# PDM-S05-V00-TempSensor.net
KiCad netlist of a schematic drawn in Altium Designer
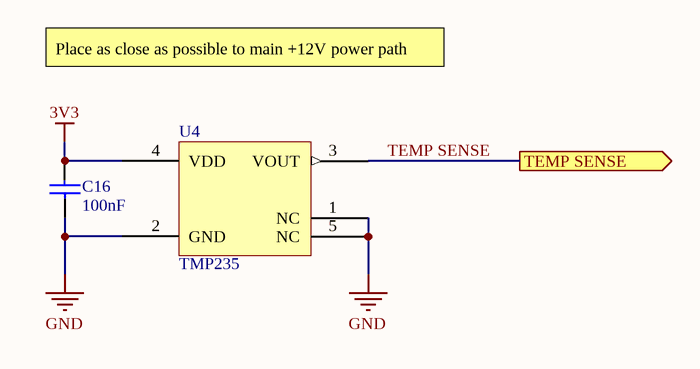
[diagram p0: PDM-S05-V00-TempSensor.SchDoc]

(export (version "E")
  (design (tool "Eeschema 10.0.6"))
  (components
    (comp (ref "C16")
      (value "100nF")
      (footprint "Cap_Ceramic_0603")
      (description "Capacitor, Ceramic, SMD, 100nF, 50V, 5%, X7R, 0603")
      (libsource (lib "StandardCapacitors") (part "100nF 50V 5% X7R 0603"))
    )
    (comp (ref "U4")
      (value "TMP235")
      (footprint "SC70")
      (description "TMP235, Low-Power, High-Accuracy Analog Output Temperature Sensor")
      (libsource (lib "PDM-CARD-SCHLib-V00") (part "TMP235"))
    )
  )
  (nets
    (net (code "1") (name "/TEMP SENSE") (class "Default")
      (node (ref "U4") (pin "3") (pinfunction "VOUT_3") (pintype "output"))
    )
    (net (code "2") (name "3V3") (class "Default")
      (node (ref "C16") (pin "2") (pinfunction "2_2") (pintype "passive"))
      (node (ref "U4") (pin "4") (pinfunction "VDD_4") (pintype "passive"))
    )
    (net (code "3") (name "GND") (class "Default")
      (node (ref "C16") (pin "1") (pinfunction "1_1") (pintype "passive"))
      (node (ref "U4") (pin "1") (pinfunction "NC_1") (pintype "passive"))
      (node (ref "U4") (pin "2") (pinfunction "GND_2") (pintype "passive"))
      (node (ref "U4") (pin "5") (pinfunction "NC_5") (pintype "passive"))
    )
  )
)
